# Addon-mapleCUx_HM-RFM69-012.net
KiCad netlist of a schematic drawn in EAGLE
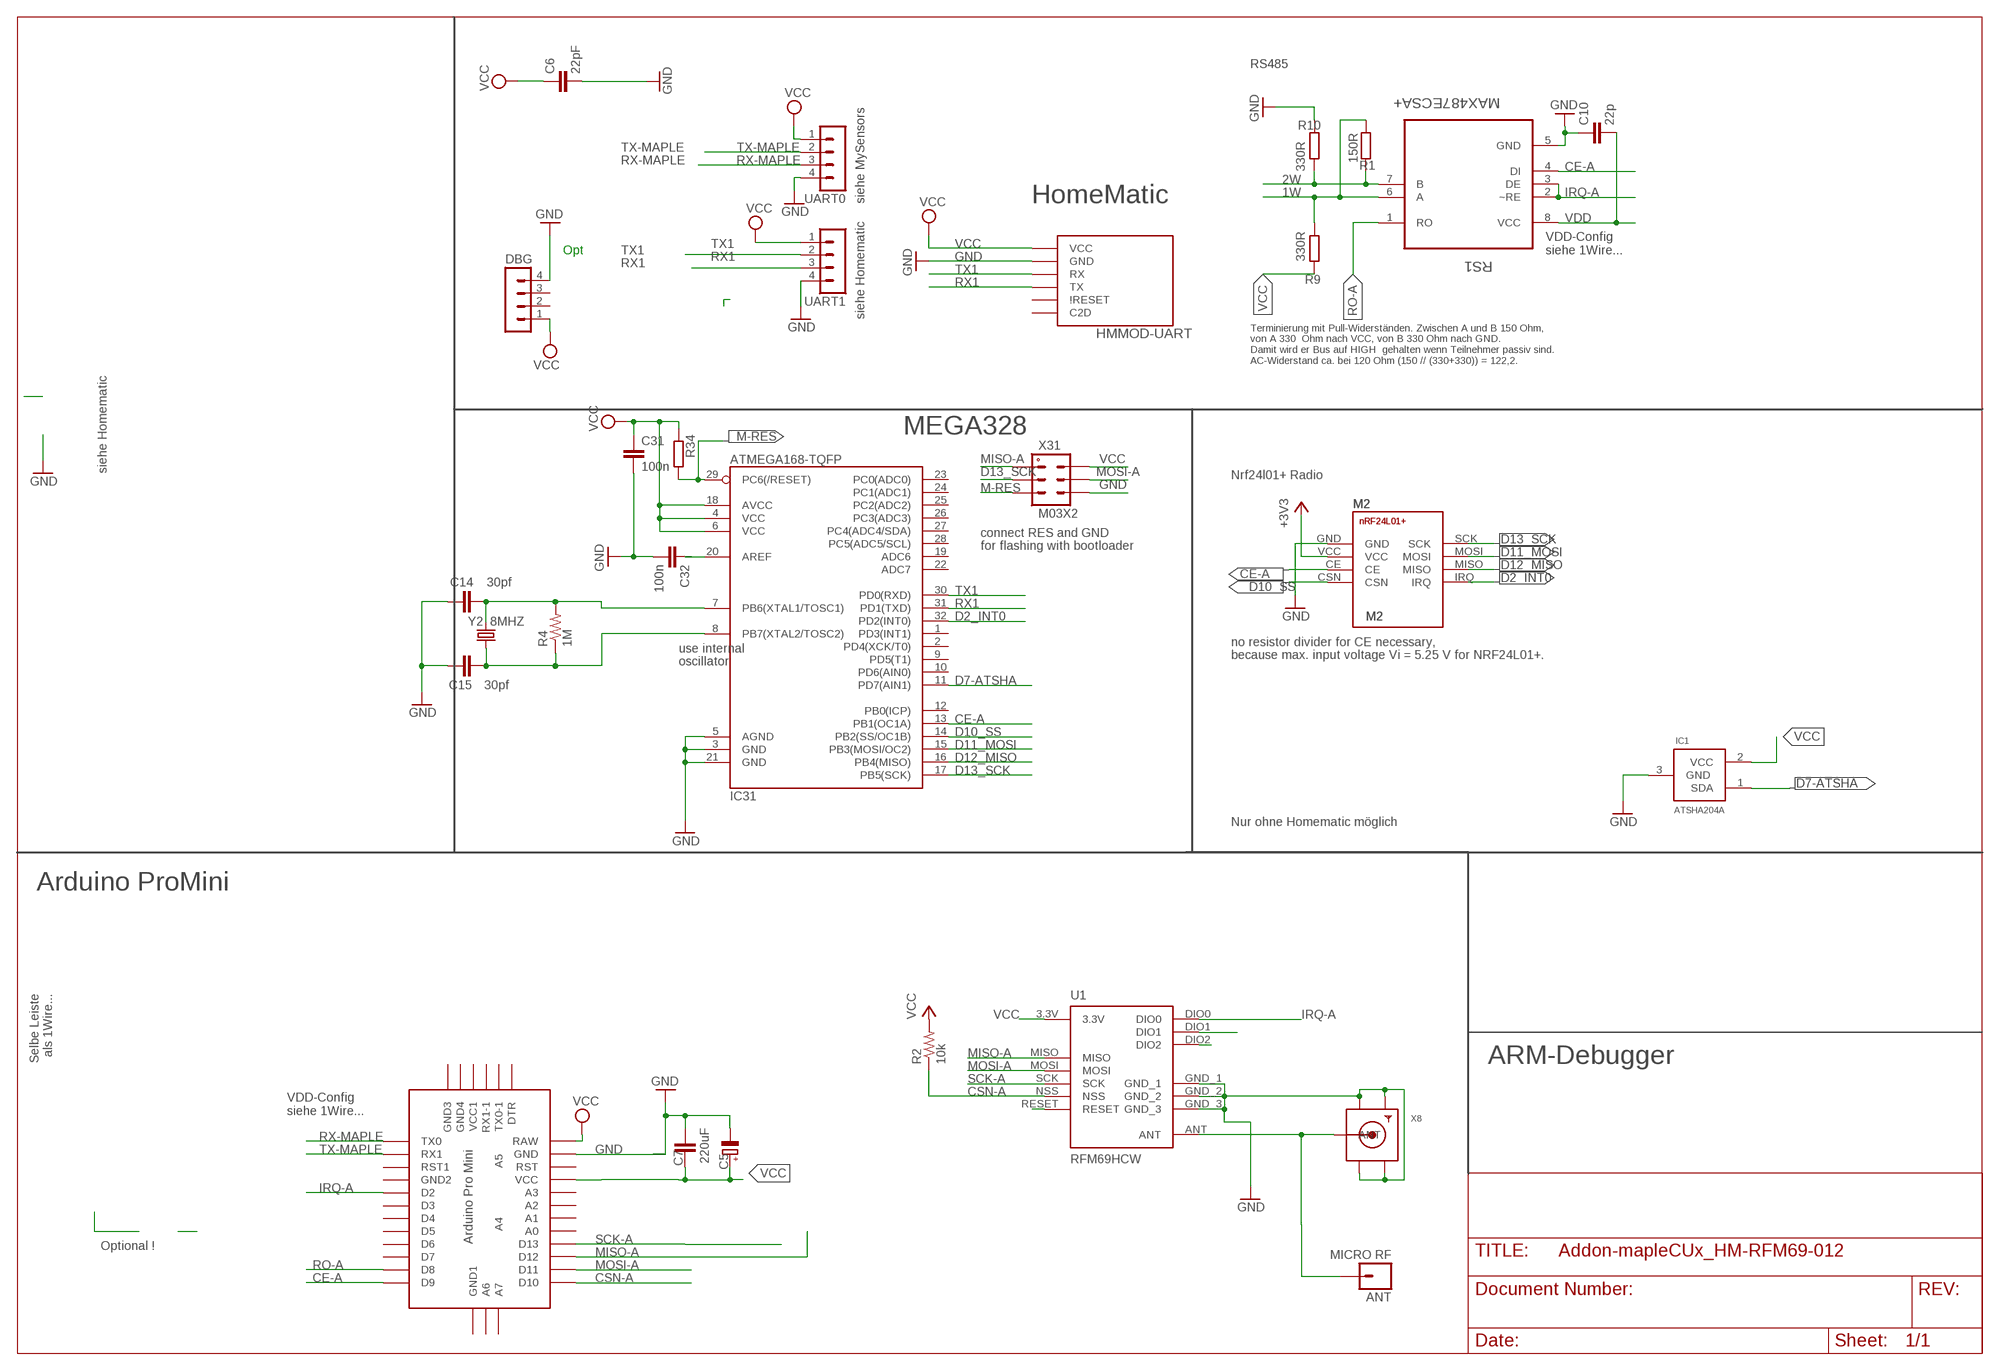
[diagram p0: schematic, sheet 1, part 1 of 2]
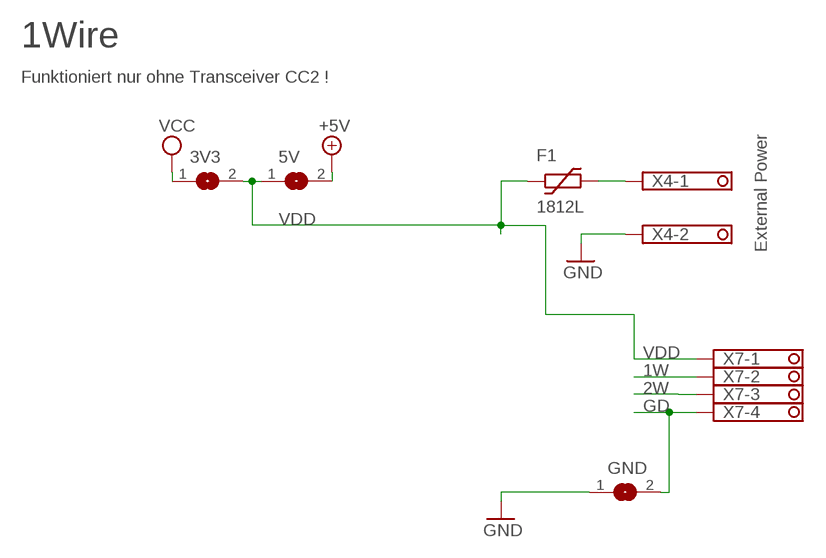
[diagram p1: schematic, sheet 1, part 2 of 2]

(export (version "E")
  (design (tool "Eeschema 10.0.6"))
  (components
    (comp (ref "3V3") (value "SJ") (footprint "eagle-import:SJ") (libsource (lib "eagle-import") (part "SJ")))
    (comp (ref "5V") (value "SJ") (footprint "eagle-import:SJ") (libsource (lib "eagle-import") (part "SJ")))
    (comp (ref "ANT")
      (value "MICRO RF")
      (footprint "eagle-import:1X01")
      (libsource (lib "eagle-import") (part "M01PTH"))
    )
    (comp (ref "C5")
      (value "220uF")
      (footprint "eagle-import:E5-8,5")
      (libsource (lib "eagle-import") (part "CPOL-EUE5-8.5"))
    )
    (comp (ref "C6")
      (value "22pF")
      (footprint "eagle-import:C0805")
      (libsource (lib "eagle-import") (part "C-EUC0805"))
    )
    (comp (ref "C7")
      (value "C-EUC1812")
      (footprint "eagle-import:C1812")
      (libsource (lib "eagle-import") (part "C-EUC1812"))
    )
    (comp (ref "C10")
      (value "22p")
      (footprint "eagle-import:C0805")
      (libsource (lib "eagle-import") (part "C-EUC0805"))
    )
    (comp (ref "C14")
      (value "30pf")
      (footprint "eagle-import:0805")
      (libsource (lib "eagle-import") (part "CAP0805"))
    )
    (comp (ref "C15")
      (value "30pf")
      (footprint "eagle-import:0805")
      (libsource (lib "eagle-import") (part "CAP0805"))
    )
    (comp (ref "C31")
      (value "100n")
      (footprint "eagle-import:C0805")
      (libsource (lib "eagle-import") (part "C-EUC0805"))
    )
    (comp (ref "C32")
      (value "100n")
      (footprint "eagle-import:C0805")
      (libsource (lib "eagle-import") (part "C-EUC0805"))
    )
    (comp (ref "DBG")
      (value "MA04-1")
      (footprint "eagle-import:MA04-1")
      (libsource (lib "eagle-import") (part "MA04-1"))
    )
    (comp (ref "F1")
      (value "1812L")
      (footprint "eagle-import:1812L")
      (libsource (lib "eagle-import") (part "1812L"))
    )
    (comp (ref "GND") (value "SJ") (footprint "eagle-import:SJ") (libsource (lib "eagle-import") (part "SJ")))
    (comp (ref "HMMOD-UART")
      (value "HM-MOD-UARTDIL")
      (footprint "eagle-import:HM-MOD-UART-DIL")
      (libsource (lib "eagle-import") (part "HM-MOD-UARTDIL"))
    )
    (comp (ref "IC1")
      (value "ATSHA204A")
      (footprint "eagle-import:SOT23")
      (libsource (lib "eagle-import") (part "ATSHA204A"))
    )
    (comp (ref "IC31")
      (value "ATMEGA168-TQFP")
      (footprint "eagle-import:TQFP32-08")
      (libsource (lib "eagle-import") (part "ATMEGA168-TQFP"))
    )
    (comp (ref "M2")
      (value "NRF24L01+SMD")
      (footprint "eagle-import:NRF24L01+SMD")
      (libsource (lib "eagle-import") (part "NRF24L01+SMD"))
    )
    (comp (ref "R1")
      (value "150R")
      (footprint "eagle-import:R0805")
      (libsource (lib "eagle-import") (part "R-EU_R0805"))
    )
    (comp (ref "R2")
      (value "10k")
      (footprint "eagle-import:0805")
      (libsource (lib "eagle-import") (part "RESISTOR0805-RES"))
    )
    (comp (ref "R4")
      (value "1M")
      (footprint "eagle-import:0805")
      (libsource (lib "eagle-import") (part "RESISTOR0805-RES"))
    )
    (comp (ref "R9")
      (value "330R")
      (footprint "eagle-import:R0805")
      (libsource (lib "eagle-import") (part "R-EU_R0805"))
    )
    (comp (ref "R10")
      (value "330R")
      (footprint "eagle-import:R0805")
      (libsource (lib "eagle-import") (part "R-EU_R0805"))
    )
    (comp (ref "R34")
      (value "R-EU_R0805")
      (footprint "eagle-import:R0805")
      (libsource (lib "eagle-import") (part "R-EU_R0805"))
    )
    (comp (ref "RS1")
      (value "MAX487ECSA+")
      (footprint "eagle-import:SOIC127P600X175-8N")
      (libsource (lib "eagle-import") (part "MAX487ECSA+"))
    )
    (comp (ref "U$2")
      (value "ABK-PRO-MINI")
      (footprint "eagle-import:ABK-PRO-MINI")
      (libsource (lib "eagle-import") (part "ABK-PRO-MINI"))
    )
    (comp (ref "U1")
      (value "RFM69HCW")
      (footprint "eagle-import:RFM69HCW-XXXS2")
      (libsource (lib "eagle-import") (part "RFM69HCW"))
    )
    (comp (ref "UART0")
      (value "MA04-1")
      (footprint "eagle-import:MA04-1")
      (libsource (lib "eagle-import") (part "MA04-1"))
    )
    (comp (ref "UART1")
      (value "MA04-1")
      (footprint "eagle-import:MA04-1")
      (libsource (lib "eagle-import") (part "MA04-1"))
    )
    (comp (ref "X4")
      (value "1751248")
      (footprint "eagle-import:1751248")
      (libsource (lib "eagle-import") (part "1751248"))
    )
    (comp (ref "X7")
      (value "1751264")
      (footprint "eagle-import:1751264")
      (libsource (lib "eagle-import") (part "1751264"))
    )
    (comp (ref "X8")
      (value "SMACONNECTOR_EDGE")
      (footprint "eagle-import:SMA_EDGELAUNCH")
      (libsource (lib "eagle-import") (part "SMACONNECTOR_EDGE"))
    )
    (comp (ref "X31")
      (value "M03X2")
      (footprint "eagle-import:2X03-1.27MM_SMD")
      (libsource (lib "eagle-import") (part "M03X2"))
    )
    (comp (ref "Y2")
      (value "8MHZ")
      (footprint "eagle-import:CRYSTAL-TXC-7A")
      (libsource (lib "eagle-import") (part "CRYSTALTXC-7A"))
    )
  )
  (nets
    (net (code "1") (name "+3V3") (class "Default")
      (node (ref "M2") (pin "VCC") (pinfunction "VCC_VCC") (pintype "power_in"))
    )
    (net (code "2") (name "+5V") (class "Default")
      (node (ref "5V") (pin "2") (pinfunction "2_2") (pintype "passive"))
    )
    (net (code "3") (name "/1W") (class "Default")
      (node (ref "R1") (pin "1") (pinfunction "1_1") (pintype "passive"))
      (node (ref "R9") (pin "2") (pinfunction "2_2") (pintype "passive"))
      (node (ref "RS1") (pin "6") (pinfunction "A_6") (pintype "bidirectional"))
      (node (ref "X7") (pin "2") (pinfunction "K_2") (pintype "passive"))
    )
    (net (code "4") (name "/2W") (class "Default")
      (node (ref "R1") (pin "2") (pinfunction "2_2") (pintype "passive"))
      (node (ref "R10") (pin "1") (pinfunction "1_1") (pintype "passive"))
      (node (ref "RS1") (pin "7") (pinfunction "B_7") (pintype "bidirectional"))
      (node (ref "X7") (pin "3") (pinfunction "K_3") (pintype "passive"))
    )
    (net (code "5") (name "/CE-A") (class "Default")
      (node (ref "IC31") (pin "13") (pinfunction "PB1(OC1A)_13") (pintype "bidirectional"))
      (node (ref "M2") (pin "CE") (pinfunction "CE_CE") (pintype "bidirectional"))
      (node (ref "RS1") (pin "4") (pinfunction "DI_4") (pintype "input"))
      (node (ref "U$2") (pin "D9") (pinfunction "D9_D9") (pintype "bidirectional"))
    )
    (net (code "6") (name "/CSN-A") (class "Default")
      (node (ref "R2") (pin "1") (pinfunction "1_1") (pintype "passive"))
      (node (ref "U$2") (pin "D10") (pinfunction "D10_D10") (pintype "bidirectional"))
      (node (ref "U1") (pin "NSS") (pinfunction "NSS_NSS") (pintype "input"))
    )
    (net (code "7") (name "/D2_INT0") (class "Default")
      (node (ref "IC31") (pin "32") (pinfunction "PD2(INT0)_32") (pintype "bidirectional"))
      (node (ref "M2") (pin "IRQ") (pinfunction "IRQ_IRQ") (pintype "bidirectional"))
    )
    (net (code "8") (name "/D7-ATSHA") (class "Default")
      (node (ref "IC1") (pin "1") (pinfunction "SDA_1") (pintype "bidirectional"))
      (node (ref "IC31") (pin "11") (pinfunction "PD7(AIN1)_11") (pintype "bidirectional"))
    )
    (net (code "9") (name "/D10_SS") (class "Default")
      (node (ref "IC31") (pin "14") (pinfunction "PB2(SS/OC1B)_14") (pintype "bidirectional"))
      (node (ref "M2") (pin "CSN") (pinfunction "CSN_CSN") (pintype "bidirectional"))
    )
    (net (code "10") (name "/D11_MOSI") (class "Default")
      (node (ref "IC31") (pin "15") (pinfunction "PB3(MOSI/OC2)_15") (pintype "bidirectional"))
      (node (ref "M2") (pin "MOSI") (pinfunction "MOSI_MOSI") (pintype "bidirectional"))
    )
    (net (code "11") (name "/D12_MISO") (class "Default")
      (node (ref "IC31") (pin "16") (pinfunction "PB4(MISO)_16") (pintype "bidirectional"))
      (node (ref "M2") (pin "MISO") (pinfunction "MISO_MISO") (pintype "bidirectional"))
    )
    (net (code "12") (name "/D13_SCK") (class "Default")
      (node (ref "IC31") (pin "17") (pinfunction "PB5(SCK)_17") (pintype "bidirectional"))
      (node (ref "M2") (pin "SCK") (pinfunction "SCK_SCK") (pintype "bidirectional"))
      (node (ref "X31") (pin "P$3") (pinfunction "3_P$3") (pintype "passive"))
    )
    (net (code "13") (name "/GD") (class "Default")
      (node (ref "GND") (pin "2") (pinfunction "2_2") (pintype "passive"))
      (node (ref "X7") (pin "4") (pinfunction "K_4") (pintype "passive"))
    )
    (net (code "14") (name "/IRQ-A") (class "Default")
      (node (ref "RS1") (pin "2") (pinfunction "~{RE}_2") (pintype "input"))
      (node (ref "RS1") (pin "3") (pinfunction "DE_3") (pintype "input"))
      (node (ref "U$2") (pin "D2") (pinfunction "D2_D2") (pintype "bidirectional"))
      (node (ref "U1") (pin "DIO0") (pinfunction "DIO0_DIO0") (pintype "bidirectional"))
    )
    (net (code "15") (name "/M-RES") (class "Default")
      (node (ref "IC31") (pin "29") (pinfunction "PC6(/RESET)_29") (pintype "bidirectional"))
      (node (ref "R34") (pin "2") (pinfunction "2_2") (pintype "passive"))
      (node (ref "X31") (pin "P$5") (pinfunction "5_P$5") (pintype "passive"))
    )
    (net (code "16") (name "/MISO-A") (class "Default")
      (node (ref "U$2") (pin "D12") (pinfunction "D12_D12") (pintype "bidirectional"))
      (node (ref "U1") (pin "MISO") (pinfunction "MISO_MISO") (pintype "bidirectional"))
      (node (ref "X31") (pin "P$1") (pinfunction "1_P$1") (pintype "passive"))
    )
    (net (code "17") (name "/MOSI-A") (class "Default")
      (node (ref "U$2") (pin "D11") (pinfunction "D11_D11") (pintype "bidirectional"))
      (node (ref "U1") (pin "MOSI") (pinfunction "MOSI_MOSI") (pintype "input"))
      (node (ref "X31") (pin "P$4") (pinfunction "4_P$4") (pintype "passive"))
    )
    (net (code "18") (name "/RX-MAPLE") (class "Default")
      (node (ref "U$2") (pin "TX0") (pinfunction "TX0_TX0") (pintype "bidirectional"))
      (node (ref "UART0") (pin "3") (pinfunction "3_3") (pintype "passive"))
    )
    (net (code "19") (name "/RX1") (class "Default")
      (node (ref "HMMOD-UART") (pin "5") (pinfunction "TX_5") (pintype "bidirectional"))
      (node (ref "IC31") (pin "31") (pinfunction "PD1(TXD)_31") (pintype "bidirectional"))
      (node (ref "UART1") (pin "3") (pinfunction "3_3") (pintype "passive"))
    )
    (net (code "20") (name "/SCK-A") (class "Default")
      (node (ref "U$2") (pin "D13") (pinfunction "D13_D13") (pintype "bidirectional"))
      (node (ref "U1") (pin "SCK") (pinfunction "SCK_SCK") (pintype "input"))
    )
    (net (code "21") (name "/TX-MAPLE") (class "Default")
      (node (ref "U$2") (pin "RX1") (pinfunction "RX1_RX1") (pintype "bidirectional"))
      (node (ref "UART0") (pin "2") (pinfunction "2_2") (pintype "passive"))
    )
    (net (code "22") (name "/TX1") (class "Default")
      (node (ref "HMMOD-UART") (pin "6") (pinfunction "RX_6") (pintype "bidirectional"))
      (node (ref "IC31") (pin "30") (pinfunction "PD0(RXD)_30") (pintype "bidirectional"))
      (node (ref "UART1") (pin "2") (pinfunction "2_2") (pintype "passive"))
    )
    (net (code "23") (name "/VDD") (class "Default")
      (node (ref "3V3") (pin "2") (pinfunction "2_2") (pintype "passive"))
      (node (ref "5V") (pin "1") (pinfunction "1_1") (pintype "passive"))
      (node (ref "C10") (pin "2") (pinfunction "2_2") (pintype "passive"))
      (node (ref "F1") (pin "P$1") (pinfunction "1_P$1") (pintype "passive"))
      (node (ref "RS1") (pin "8") (pinfunction "VCC_8") (pintype "power_in"))
      (node (ref "X7") (pin "1") (pinfunction "K_1") (pintype "passive"))
    )
    (net (code "24") (name "GND") (class "Default")
      (node (ref "C10") (pin "1") (pinfunction "1_1") (pintype "passive"))
      (node (ref "C14") (pin "1") (pinfunction "1_1") (pintype "passive"))
      (node (ref "C15") (pin "1") (pinfunction "1_1") (pintype "passive"))
      (node (ref "C31") (pin "2") (pinfunction "2_2") (pintype "passive"))
      (node (ref "C32") (pin "2") (pinfunction "2_2") (pintype "passive"))
      (node (ref "C5") (pin "-") (pinfunction "-_-") (pintype "passive"))
      (node (ref "C6") (pin "2") (pinfunction "2_2") (pintype "passive"))
      (node (ref "C7") (pin "1") (pinfunction "1_1") (pintype "passive"))
      (node (ref "DBG") (pin "4") (pinfunction "4_4") (pintype "passive"))
      (node (ref "GND") (pin "1") (pinfunction "1_1") (pintype "passive"))
      (node (ref "HMMOD-UART") (pin "2") (pinfunction "GND_2") (pintype "power_in"))
      (node (ref "IC1") (pin "3") (pinfunction "GND_3") (pintype "bidirectional"))
      (node (ref "IC31") (pin "21") (pinfunction "GND_21") (pintype "bidirectional"))
      (node (ref "IC31") (pin "3") (pinfunction "GND_3") (pintype "bidirectional"))
      (node (ref "IC31") (pin "5") (pinfunction "AGND_5") (pintype "bidirectional"))
      (node (ref "M2") (pin "GND") (pinfunction "GND_GND") (pintype "power_in"))
      (node (ref "R10") (pin "2") (pinfunction "2_2") (pintype "passive"))
      (node (ref "RS1") (pin "5") (pinfunction "GND_5") (pintype "passive"))
      (node (ref "U$2") (pin "GND") (pinfunction "GND_GND") (pintype "bidirectional"))
      (node (ref "U1") (pin "GND_1") (pinfunction "GND_1_GND_1") (pintype "power_in"))
      (node (ref "U1") (pin "GND_2") (pinfunction "GND_2_GND_2") (pintype "power_in"))
      (node (ref "U1") (pin "GND_3") (pinfunction "GND_3_GND_3") (pintype "power_in"))
      (node (ref "UART0") (pin "4") (pinfunction "4_4") (pintype "passive"))
      (node (ref "UART1") (pin "4") (pinfunction "4_4") (pintype "passive"))
      (node (ref "X31") (pin "P$6") (pinfunction "6_P$6") (pintype "passive"))
      (node (ref "X4") (pin "2") (pinfunction "K_2") (pintype "passive"))
      (node (ref "X8") (pin "GND@1") (pinfunction "GND4_GND@1") (pintype "power_in"))
      (node (ref "X8") (pin "GND@2") (pinfunction "GND3_GND@2") (pintype "power_in"))
      (node (ref "X8") (pin "GND@3") (pinfunction "GND2_GND@3") (pintype "power_in"))
      (node (ref "X8") (pin "GND@4") (pinfunction "GND1_GND@4") (pintype "power_in"))
    )
    (net (code "25") (name "Net-(F1-2)") (class "Default")
      (node (ref "F1") (pin "P$2") (pinfunction "2_P$2") (pintype "passive"))
      (node (ref "X4") (pin "1") (pinfunction "K_1") (pintype "passive"))
    )
    (net (code "26") (name "Net-(IC31-AREF)") (class "Default")
      (node (ref "C32") (pin "1") (pinfunction "1_1") (pintype "passive"))
      (node (ref "IC31") (pin "20") (pinfunction "AREF_20") (pintype "bidirectional"))
    )
    (net (code "27") (name "Net-(IC31-PB6(XTAL1{slash}TOSC1))") (class "Default")
      (node (ref "C14") (pin "2") (pinfunction "2_2") (pintype "passive"))
      (node (ref "IC31") (pin "7") (pinfunction "PB6(XTAL1/TOSC1)_7") (pintype "bidirectional"))
      (node (ref "R4") (pin "2") (pinfunction "2_2") (pintype "passive"))
      (node (ref "Y2") (pin "P$2") (pinfunction "2_P$2") (pintype "passive"))
    )
    (net (code "28") (name "Net-(IC31-PB7(XTAL2{slash}TOSC2))") (class "Default")
      (node (ref "C15") (pin "2") (pinfunction "2_2") (pintype "passive"))
      (node (ref "IC31") (pin "8") (pinfunction "PB7(XTAL2/TOSC2)_8") (pintype "bidirectional"))
      (node (ref "R4") (pin "1") (pinfunction "1_1") (pintype "passive"))
      (node (ref "Y2") (pin "P$1") (pinfunction "1_P$1") (pintype "passive"))
    )
    (net (code "29") (name "Net-(X8-ANT)") (class "Default")
      (node (ref "ANT") (pin "1") (pinfunction "1_1") (pintype "passive"))
      (node (ref "U1") (pin "ANT") (pinfunction "ANT_ANT") (pintype "passive"))
      (node (ref "X8") (pin "P") (pinfunction "ANT_P") (pintype "bidirectional"))
    )
    (net (code "30") (name "RO-A") (class "Default")
      (node (ref "RS1") (pin "1") (pinfunction "RO_1") (pintype "output"))
      (node (ref "U$2") (pin "D8") (pinfunction "D8_D8") (pintype "bidirectional"))
    )
    (net (code "31") (name "VCC") (class "Default")
      (node (ref "3V3") (pin "1") (pinfunction "1_1") (pintype "passive"))
      (node (ref "C31") (pin "1") (pinfunction "1_1") (pintype "passive"))
      (node (ref "C5") (pin "+") (pinfunction "+_+") (pintype "passive"))
      (node (ref "C6") (pin "1") (pinfunction "1_1") (pintype "passive"))
      (node (ref "C7") (pin "2") (pinfunction "2_2") (pintype "passive"))
      (node (ref "DBG") (pin "1") (pinfunction "1_1") (pintype "passive"))
      (node (ref "HMMOD-UART") (pin "1") (pinfunction "VCC_1") (pintype "power_in"))
      (node (ref "IC1") (pin "2") (pinfunction "VCC_2") (pintype "bidirectional"))
      (node (ref "IC31") (pin "18") (pinfunction "AVCC_18") (pintype "bidirectional"))
      (node (ref "IC31") (pin "4") (pinfunction "VCC_4") (pintype "bidirectional"))
      (node (ref "IC31") (pin "6") (pinfunction "VCC_6") (pintype "bidirectional"))
      (node (ref "R2") (pin "2") (pinfunction "2_2") (pintype "passive"))
      (node (ref "R34") (pin "1") (pinfunction "1_1") (pintype "passive"))
      (node (ref "R9") (pin "1") (pinfunction "1_1") (pintype "passive"))
      (node (ref "U$2") (pin "RAW") (pinfunction "RAW_RAW") (pintype "bidirectional"))
      (node (ref "U$2") (pin "VCC") (pinfunction "VCC_VCC") (pintype "bidirectional"))
      (node (ref "U1") (pin "3.3V") (pinfunction "3.3V_3.3V") (pintype "power_in"))
      (node (ref "UART0") (pin "1") (pinfunction "1_1") (pintype "passive"))
      (node (ref "UART1") (pin "1") (pinfunction "1_1") (pintype "passive"))
      (node (ref "X31") (pin "P$2") (pinfunction "2_P$2") (pintype "passive"))
    )
    (net (code "32") (name "unconnected-(DBG-Pad2)") (class "Default")
      (node (ref "DBG") (pin "2") (pinfunction "2_2") (pintype "passive"))
    )
    (net (code "33") (name "unconnected-(DBG-Pad3)") (class "Default")
      (node (ref "DBG") (pin "3") (pinfunction "3_3") (pintype "passive"))
    )
    (net (code "34") (name "unconnected-(HMMOD-UART-C2D-Pad3)") (class "Default")
      (node (ref "HMMOD-UART") (pin "3") (pinfunction "C2D_3") (pintype "bidirectional"))
    )
    (net (code "35") (name "unconnected-(HMMOD-UART-\\~{RESET}-Pad4)") (class "Default")
      (node (ref "HMMOD-UART") (pin "4") (pinfunction "\\~{RESET}_4") (pintype "bidirectional"))
    )
    (net (code "36") (name "unconnected-(IC31-ADC6-Pad19)") (class "Default")
      (node (ref "IC31") (pin "19") (pinfunction "ADC6_19") (pintype "bidirectional"))
    )
    (net (code "37") (name "unconnected-(IC31-ADC7-Pad22)") (class "Default")
      (node (ref "IC31") (pin "22") (pinfunction "ADC7_22") (pintype "bidirectional"))
    )
    (net (code "38") (name "unconnected-(IC31-PB0(ICP)-Pad12)") (class "Default")
      (node (ref "IC31") (pin "12") (pinfunction "PB0(ICP)_12") (pintype "bidirectional"))
    )
    (net (code "39") (name "unconnected-(IC31-PC0(ADC0)-Pad23)") (class "Default")
      (node (ref "IC31") (pin "23") (pinfunction "PC0(ADC0)_23") (pintype "bidirectional"))
    )
    (net (code "40") (name "unconnected-(IC31-PC1(ADC1)-Pad24)") (class "Default")
      (node (ref "IC31") (pin "24") (pinfunction "PC1(ADC1)_24") (pintype "bidirectional"))
    )
    (net (code "41") (name "unconnected-(IC31-PC2(ADC2)-Pad25)") (class "Default")
      (node (ref "IC31") (pin "25") (pinfunction "PC2(ADC2)_25") (pintype "bidirectional"))
    )
    (net (code "42") (name "unconnected-(IC31-PC3(ADC3)-Pad26)") (class "Default")
      (node (ref "IC31") (pin "26") (pinfunction "PC3(ADC3)_26") (pintype "bidirectional"))
    )
    (net (code "43") (name "unconnected-(IC31-PC4(ADC4{slash}SDA)-Pad27)") (class "Default")
      (node (ref "IC31") (pin "27") (pinfunction "PC4(ADC4/SDA)_27") (pintype "bidirectional"))
    )
    (net (code "44") (name "unconnected-(IC31-PC5(ADC5{slash}SCL)-Pad28)") (class "Default")
      (node (ref "IC31") (pin "28") (pinfunction "PC5(ADC5/SCL)_28") (pintype "bidirectional"))
    )
    (net (code "45") (name "unconnected-(IC31-PD3(INT1)-Pad1)") (class "Default")
      (node (ref "IC31") (pin "1") (pinfunction "PD3(INT1)_1") (pintype "bidirectional"))
    )
    (net (code "46") (name "unconnected-(IC31-PD4(XCK{slash}T0)-Pad2)") (class "Default")
      (node (ref "IC31") (pin "2") (pinfunction "PD4(XCK/T0)_2") (pintype "bidirectional"))
    )
    (net (code "47") (name "unconnected-(IC31-PD5(T1)-Pad9)") (class "Default")
      (node (ref "IC31") (pin "9") (pinfunction "PD5(T1)_9") (pintype "bidirectional"))
    )
    (net (code "48") (name "unconnected-(IC31-PD6(AIN0)-Pad10)") (class "Default")
      (node (ref "IC31") (pin "10") (pinfunction "PD6(AIN0)_10") (pintype "bidirectional"))
    )
    (net (code "49") (name "unconnected-(U$2-GND1-PadGND4)") (class "Default")
      (node (ref "U$2") (pin "GND4") (pinfunction "GND1_GND4") (pintype "bidirectional"))
    )
    (net (code "50") (name "unconnected-(U$2-GND2-PadGND1)") (class "Default")
      (node (ref "U$2") (pin "GND1") (pinfunction "GND2_GND1") (pintype "bidirectional"))
    )
    (net (code "51") (name "unconnected-(U$2-GND3-PadGND2)") (class "Default")
      (node (ref "U$2") (pin "GND2") (pinfunction "GND3_GND2") (pintype "bidirectional"))
    )
    (net (code "52") (name "unconnected-(U$2-GND4-PadGND3)") (class "Default")
      (node (ref "U$2") (pin "GND3") (pinfunction "GND4_GND3") (pintype "bidirectional"))
    )
    (net (code "53") (name "unconnected-(U$2-PadA0)") (class "Default")
      (node (ref "U$2") (pin "A0") (pinfunction "A0_A0") (pintype "bidirectional"))
    )
    (net (code "54") (name "unconnected-(U$2-PadA1)") (class "Default")
      (node (ref "U$2") (pin "A1") (pinfunction "A1_A1") (pintype "bidirectional"))
    )
    (net (code "55") (name "unconnected-(U$2-PadA2)") (class "Default")
      (node (ref "U$2") (pin "A2") (pinfunction "A2_A2") (pintype "bidirectional"))
    )
    (net (code "56") (name "unconnected-(U$2-PadA3)") (class "Default")
      (node (ref "U$2") (pin "A3") (pinfunction "A3_A3") (pintype "bidirectional"))
    )
    (net (code "57") (name "unconnected-(U$2-PadA4)") (class "Default")
      (node (ref "U$2") (pin "A4") (pinfunction "A4_A4") (pintype "bidirectional"))
    )
    (net (code "58") (name "unconnected-(U$2-PadA5)") (class "Default")
      (node (ref "U$2") (pin "A5") (pinfunction "A5_A5") (pintype "bidirectional"))
    )
    (net (code "59") (name "unconnected-(U$2-PadA6)") (class "Default")
      (node (ref "U$2") (pin "A6") (pinfunction "A6_A6") (pintype "bidirectional"))
    )
    (net (code "60") (name "unconnected-(U$2-PadA7)") (class "Default")
      (node (ref "U$2") (pin "A7") (pinfunction "A7_A7") (pintype "bidirectional"))
    )
    (net (code "61") (name "unconnected-(U$2-PadD3)") (class "Default")
      (node (ref "U$2") (pin "D3") (pinfunction "D3_D3") (pintype "bidirectional"))
    )
    (net (code "62") (name "unconnected-(U$2-PadD4)") (class "Default")
      (node (ref "U$2") (pin "D4") (pinfunction "D4_D4") (pintype "bidirectional"))
    )
    (net (code "63") (name "unconnected-(U$2-PadD5)") (class "Default")
      (node (ref "U$2") (pin "D5") (pinfunction "D5_D5") (pintype "bidirectional"))
    )
    (net (code "64") (name "unconnected-(U$2-PadD6)") (class "Default")
      (node (ref "U$2") (pin "D6") (pinfunction "D6_D6") (pintype "bidirectional"))
    )
    (net (code "65") (name "unconnected-(U$2-PadD7)") (class "Default")
      (node (ref "U$2") (pin "D7") (pinfunction "D7_D7") (pintype "bidirectional"))
    )
    (net (code "66") (name "unconnected-(U$2-PadDTR)") (class "Default")
      (node (ref "U$2") (pin "DTR") (pinfunction "DTR_DTR") (pintype "bidirectional"))
    )
    (net (code "67") (name "unconnected-(U$2-PadRST)") (class "Default")
      (node (ref "U$2") (pin "RST") (pinfunction "RST_RST") (pintype "bidirectional"))
    )
    (net (code "68") (name "unconnected-(U$2-PadRST1)") (class "Default")
      (node (ref "U$2") (pin "RST1") (pinfunction "RST1_RST1") (pintype "bidirectional"))
    )
    (net (code "69") (name "unconnected-(U$2-PadRX1-1)") (class "Default")
      (node (ref "U$2") (pin "RX1-1") (pinfunction "RX1-1_RX1-1") (pintype "bidirectional"))
    )
    (net (code "70") (name "unconnected-(U$2-PadTX0-1)") (class "Default")
      (node (ref "U$2") (pin "TX0-1") (pinfunction "TX0-1_TX0-1") (pintype "bidirectional"))
    )
    (net (code "71") (name "unconnected-(U$2-PadVCC1)") (class "Default")
      (node (ref "U$2") (pin "VCC1") (pinfunction "VCC1_VCC1") (pintype "bidirectional"))
    )
    (net (code "72") (name "unconnected-(U1-PadDIO1)") (class "Default")
      (node (ref "U1") (pin "DIO1") (pinfunction "DIO1_DIO1") (pintype "bidirectional"))
    )
    (net (code "73") (name "unconnected-(U1-PadDIO2)") (class "Default")
      (node (ref "U1") (pin "DIO2") (pinfunction "DIO2_DIO2") (pintype "bidirectional"))
    )
    (net (code "74") (name "unconnected-(U1-PadRESET)") (class "Default")
      (node (ref "U1") (pin "RESET") (pinfunction "RESET_RESET") (pintype "input"))
    )
  )
)
